# Base.net
KiCad netlist of a schematic drawn in EAGLE
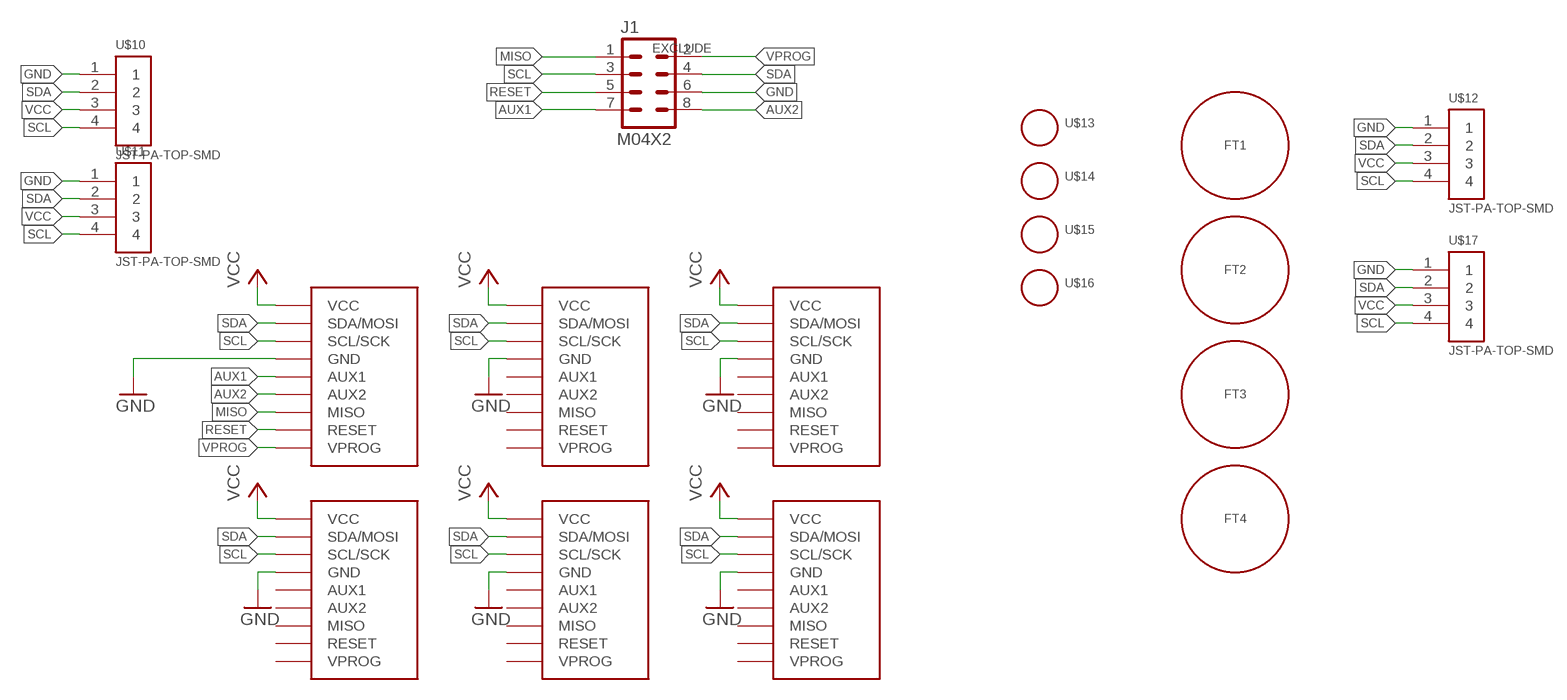
[diagram p0: schematic, sheet 1]

(export (version "E")
  (design (tool "Eeschema 10.0.6"))
  (components
    (comp (ref "FT1")
      (value "FOOT")
      (footprint "eagle-import:FOOT")
      (fields (field (name "PARTNUM") "SJ6553"))
      (libsource (lib "eagle-import") (part "FOOT"))
    )
    (comp (ref "FT2")
      (value "FOOT")
      (footprint "eagle-import:FOOT")
      (fields (field (name "PARTNUM") "SJ6553"))
      (libsource (lib "eagle-import") (part "FOOT"))
    )
    (comp (ref "FT3")
      (value "FOOT")
      (footprint "eagle-import:FOOT")
      (fields (field (name "PARTNUM") "SJ6553"))
      (libsource (lib "eagle-import") (part "FOOT"))
    )
    (comp (ref "FT4")
      (value "FOOT")
      (footprint "eagle-import:FOOT")
      (fields (field (name "PARTNUM") "SJ6553"))
      (libsource (lib "eagle-import") (part "FOOT"))
    )
    (comp (ref "J1")
      (value "M04X2")
      (footprint "eagle-import:2X4")
      (fields (field (name "PARTNUM") "EXCLUDE"))
      (libsource (lib "eagle-import") (part "M04X2"))
    )
    (comp (ref "U$1")
      (value "MAGBASE-V2")
      (footprint "eagle-import:MAGBASE-V2")
      (libsource (lib "eagle-import") (part "MAGBASE-V2"))
    )
    (comp (ref "U$2")
      (value "MAGBASE-V2")
      (footprint "eagle-import:MAGBASE-V2")
      (libsource (lib "eagle-import") (part "MAGBASE-V2"))
    )
    (comp (ref "U$3")
      (value "MAGBASE-V2")
      (footprint "eagle-import:MAGBASE-V2")
      (libsource (lib "eagle-import") (part "MAGBASE-V2"))
    )
    (comp (ref "U$4")
      (value "MAGBASE-V2")
      (footprint "eagle-import:MAGBASE-V2")
      (libsource (lib "eagle-import") (part "MAGBASE-V2"))
    )
    (comp (ref "U$5")
      (value "MAGBASE-V2")
      (footprint "eagle-import:MAGBASE-V2")
      (libsource (lib "eagle-import") (part "MAGBASE-V2"))
    )
    (comp (ref "U$6")
      (value "MAGBASE-V2")
      (footprint "eagle-import:MAGBASE-V2")
      (libsource (lib "eagle-import") (part "MAGBASE-V2"))
    )
    (comp (ref "U$10")
      (value "JST-PA-TOP-SMD")
      (footprint "eagle-import:JST-PA-TOP-SMD")
      (fields (field (name "PARTNUM") "BM04B-PASS-1-TFT(LF)(SN)"))
      (libsource (lib "eagle-import") (part "JST-PA-TOP-SMD"))
    )
    (comp (ref "U$11")
      (value "JST-PA-TOP-SMD")
      (footprint "eagle-import:JST-PA-TOP-SMD")
      (fields (field (name "PARTNUM") "BM04B-PASS-1-TFT(LF)(SN)"))
      (libsource (lib "eagle-import") (part "JST-PA-TOP-SMD"))
    )
    (comp (ref "U$12")
      (value "JST-PA-TOP-SMD")
      (footprint "eagle-import:JST-PA-TOP-SMD")
      (fields (field (name "PARTNUM") "BM04B-PASS-1-TFT(LF)(SN)"))
      (libsource (lib "eagle-import") (part "JST-PA-TOP-SMD"))
    )
    (comp (ref "U$13")
      (value "HOLE#4")
      (footprint "eagle-import:HOLE-#4")
      (fields (field (name "PARTNUM") "EXCLUDE"))
      (libsource (lib "eagle-import") (part "HOLE#4"))
    )
    (comp (ref "U$14")
      (value "HOLE#4")
      (footprint "eagle-import:HOLE-#4")
      (fields (field (name "PARTNUM") "EXCLUDE"))
      (libsource (lib "eagle-import") (part "HOLE#4"))
    )
    (comp (ref "U$15")
      (value "HOLE#4")
      (footprint "eagle-import:HOLE-#4")
      (fields (field (name "PARTNUM") "EXCLUDE"))
      (libsource (lib "eagle-import") (part "HOLE#4"))
    )
    (comp (ref "U$16")
      (value "HOLE#4")
      (footprint "eagle-import:HOLE-#4")
      (fields (field (name "PARTNUM") "EXCLUDE"))
      (libsource (lib "eagle-import") (part "HOLE#4"))
    )
    (comp (ref "U$17")
      (value "JST-PA-TOP-SMD")
      (footprint "eagle-import:JST-PA-TOP-SMD")
      (fields (field (name "PARTNUM") "BM04B-PASS-1-TFT(LF)(SN)"))
      (libsource (lib "eagle-import") (part "JST-PA-TOP-SMD"))
    )
  )
  (nets
    (net (code "1") (name "AUX1") (class "Default")
      (node (ref "J1") (pin "7") (pinfunction "7_7") (pintype "passive"))
      (node (ref "U$1") (pin "AUX1") (pinfunction "AUX1_AUX1") (pintype "bidirectional"))
    )
    (net (code "2") (name "AUX2") (class "Default")
      (node (ref "J1") (pin "8") (pinfunction "8_8") (pintype "passive"))
      (node (ref "U$1") (pin "AUX2") (pinfunction "AUX2_AUX2") (pintype "bidirectional"))
    )
    (net (code "3") (name "GND") (class "Default")
      (node (ref "J1") (pin "6") (pinfunction "6_6") (pintype "passive"))
      (node (ref "U$1") (pin "GND") (pinfunction "GND_GND") (pintype "bidirectional"))
      (node (ref "U$10") (pin "1") (pinfunction "1_1") (pintype "bidirectional"))
      (node (ref "U$11") (pin "1") (pinfunction "1_1") (pintype "bidirectional"))
      (node (ref "U$12") (pin "1") (pinfunction "1_1") (pintype "bidirectional"))
      (node (ref "U$17") (pin "1") (pinfunction "1_1") (pintype "bidirectional"))
      (node (ref "U$2") (pin "GND") (pinfunction "GND_GND") (pintype "bidirectional"))
      (node (ref "U$3") (pin "GND") (pinfunction "GND_GND") (pintype "bidirectional"))
      (node (ref "U$4") (pin "GND") (pinfunction "GND_GND") (pintype "bidirectional"))
      (node (ref "U$5") (pin "GND") (pinfunction "GND_GND") (pintype "bidirectional"))
      (node (ref "U$6") (pin "GND") (pinfunction "GND_GND") (pintype "bidirectional"))
    )
    (net (code "4") (name "MISO") (class "Default")
      (node (ref "J1") (pin "1") (pinfunction "1_1") (pintype "passive"))
      (node (ref "U$1") (pin "MISO") (pinfunction "MISO_MISO") (pintype "bidirectional"))
    )
    (net (code "5") (name "RESET") (class "Default")
      (node (ref "J1") (pin "5") (pinfunction "5_5") (pintype "passive"))
      (node (ref "U$1") (pin "RESET") (pinfunction "RESET_RESET") (pintype "bidirectional"))
    )
    (net (code "6") (name "SCL") (class "Default")
      (node (ref "J1") (pin "3") (pinfunction "3_3") (pintype "passive"))
      (node (ref "U$1") (pin "SCL") (pinfunction "SCL/SCK_SCL") (pintype "bidirectional"))
      (node (ref "U$10") (pin "4") (pinfunction "4_4") (pintype "bidirectional"))
      (node (ref "U$11") (pin "4") (pinfunction "4_4") (pintype "bidirectional"))
      (node (ref "U$12") (pin "4") (pinfunction "4_4") (pintype "bidirectional"))
      (node (ref "U$17") (pin "4") (pinfunction "4_4") (pintype "bidirectional"))
      (node (ref "U$2") (pin "SCL") (pinfunction "SCL/SCK_SCL") (pintype "bidirectional"))
      (node (ref "U$3") (pin "SCL") (pinfunction "SCL/SCK_SCL") (pintype "bidirectional"))
      (node (ref "U$4") (pin "SCL") (pinfunction "SCL/SCK_SCL") (pintype "bidirectional"))
      (node (ref "U$5") (pin "SCL") (pinfunction "SCL/SCK_SCL") (pintype "bidirectional"))
      (node (ref "U$6") (pin "SCL") (pinfunction "SCL/SCK_SCL") (pintype "bidirectional"))
    )
    (net (code "7") (name "SDA") (class "Default")
      (node (ref "J1") (pin "4") (pinfunction "4_4") (pintype "passive"))
      (node (ref "U$1") (pin "SDA") (pinfunction "SDA/MOSI_SDA") (pintype "bidirectional"))
      (node (ref "U$10") (pin "2") (pinfunction "2_2") (pintype "bidirectional"))
      (node (ref "U$11") (pin "2") (pinfunction "2_2") (pintype "bidirectional"))
      (node (ref "U$12") (pin "2") (pinfunction "2_2") (pintype "bidirectional"))
      (node (ref "U$17") (pin "2") (pinfunction "2_2") (pintype "bidirectional"))
      (node (ref "U$2") (pin "SDA") (pinfunction "SDA/MOSI_SDA") (pintype "bidirectional"))
      (node (ref "U$3") (pin "SDA") (pinfunction "SDA/MOSI_SDA") (pintype "bidirectional"))
      (node (ref "U$4") (pin "SDA") (pinfunction "SDA/MOSI_SDA") (pintype "bidirectional"))
      (node (ref "U$5") (pin "SDA") (pinfunction "SDA/MOSI_SDA") (pintype "bidirectional"))
      (node (ref "U$6") (pin "SDA") (pinfunction "SDA/MOSI_SDA") (pintype "bidirectional"))
    )
    (net (code "8") (name "VCC") (class "Default")
      (node (ref "U$1") (pin "VCC") (pinfunction "VCC_VCC") (pintype "bidirectional"))
      (node (ref "U$10") (pin "3") (pinfunction "3_3") (pintype "bidirectional"))
      (node (ref "U$11") (pin "3") (pinfunction "3_3") (pintype "bidirectional"))
      (node (ref "U$12") (pin "3") (pinfunction "3_3") (pintype "bidirectional"))
      (node (ref "U$17") (pin "3") (pinfunction "3_3") (pintype "bidirectional"))
      (node (ref "U$2") (pin "VCC") (pinfunction "VCC_VCC") (pintype "bidirectional"))
      (node (ref "U$3") (pin "VCC") (pinfunction "VCC_VCC") (pintype "bidirectional"))
      (node (ref "U$4") (pin "VCC") (pinfunction "VCC_VCC") (pintype "bidirectional"))
      (node (ref "U$5") (pin "VCC") (pinfunction "VCC_VCC") (pintype "bidirectional"))
      (node (ref "U$6") (pin "VCC") (pinfunction "VCC_VCC") (pintype "bidirectional"))
    )
    (net (code "9") (name "VPROG") (class "Default")
      (node (ref "J1") (pin "2") (pinfunction "2_2") (pintype "passive"))
      (node (ref "U$1") (pin "VPROG") (pinfunction "VPROG_VPROG") (pintype "bidirectional"))
    )
    (net (code "10") (name "unconnected-(U$2-PadAUX1)") (class "Default")
      (node (ref "U$2") (pin "AUX1") (pinfunction "AUX1_AUX1") (pintype "bidirectional"))
    )
    (net (code "11") (name "unconnected-(U$2-PadAUX2)") (class "Default")
      (node (ref "U$2") (pin "AUX2") (pinfunction "AUX2_AUX2") (pintype "bidirectional"))
    )
    (net (code "12") (name "unconnected-(U$2-PadMISO)") (class "Default")
      (node (ref "U$2") (pin "MISO") (pinfunction "MISO_MISO") (pintype "bidirectional"))
    )
    (net (code "13") (name "unconnected-(U$2-PadRESET)") (class "Default")
      (node (ref "U$2") (pin "RESET") (pinfunction "RESET_RESET") (pintype "bidirectional"))
    )
    (net (code "14") (name "unconnected-(U$2-PadVPROG)") (class "Default")
      (node (ref "U$2") (pin "VPROG") (pinfunction "VPROG_VPROG") (pintype "bidirectional"))
    )
    (net (code "15") (name "unconnected-(U$3-PadAUX1)") (class "Default")
      (node (ref "U$3") (pin "AUX1") (pinfunction "AUX1_AUX1") (pintype "bidirectional"))
    )
    (net (code "16") (name "unconnected-(U$3-PadAUX2)") (class "Default")
      (node (ref "U$3") (pin "AUX2") (pinfunction "AUX2_AUX2") (pintype "bidirectional"))
    )
    (net (code "17") (name "unconnected-(U$3-PadMISO)") (class "Default")
      (node (ref "U$3") (pin "MISO") (pinfunction "MISO_MISO") (pintype "bidirectional"))
    )
    (net (code "18") (name "unconnected-(U$3-PadRESET)") (class "Default")
      (node (ref "U$3") (pin "RESET") (pinfunction "RESET_RESET") (pintype "bidirectional"))
    )
    (net (code "19") (name "unconnected-(U$3-PadVPROG)") (class "Default")
      (node (ref "U$3") (pin "VPROG") (pinfunction "VPROG_VPROG") (pintype "bidirectional"))
    )
    (net (code "20") (name "unconnected-(U$4-PadAUX1)") (class "Default")
      (node (ref "U$4") (pin "AUX1") (pinfunction "AUX1_AUX1") (pintype "bidirectional"))
    )
    (net (code "21") (name "unconnected-(U$4-PadAUX2)") (class "Default")
      (node (ref "U$4") (pin "AUX2") (pinfunction "AUX2_AUX2") (pintype "bidirectional"))
    )
    (net (code "22") (name "unconnected-(U$4-PadMISO)") (class "Default")
      (node (ref "U$4") (pin "MISO") (pinfunction "MISO_MISO") (pintype "bidirectional"))
    )
    (net (code "23") (name "unconnected-(U$4-PadRESET)") (class "Default")
      (node (ref "U$4") (pin "RESET") (pinfunction "RESET_RESET") (pintype "bidirectional"))
    )
    (net (code "24") (name "unconnected-(U$4-PadVPROG)") (class "Default")
      (node (ref "U$4") (pin "VPROG") (pinfunction "VPROG_VPROG") (pintype "bidirectional"))
    )
    (net (code "25") (name "unconnected-(U$5-PadAUX1)") (class "Default")
      (node (ref "U$5") (pin "AUX1") (pinfunction "AUX1_AUX1") (pintype "bidirectional"))
    )
    (net (code "26") (name "unconnected-(U$5-PadAUX2)") (class "Default")
      (node (ref "U$5") (pin "AUX2") (pinfunction "AUX2_AUX2") (pintype "bidirectional"))
    )
    (net (code "27") (name "unconnected-(U$5-PadMISO)") (class "Default")
      (node (ref "U$5") (pin "MISO") (pinfunction "MISO_MISO") (pintype "bidirectional"))
    )
    (net (code "28") (name "unconnected-(U$5-PadRESET)") (class "Default")
      (node (ref "U$5") (pin "RESET") (pinfunction "RESET_RESET") (pintype "bidirectional"))
    )
    (net (code "29") (name "unconnected-(U$5-PadVPROG)") (class "Default")
      (node (ref "U$5") (pin "VPROG") (pinfunction "VPROG_VPROG") (pintype "bidirectional"))
    )
    (net (code "30") (name "unconnected-(U$6-PadAUX1)") (class "Default")
      (node (ref "U$6") (pin "AUX1") (pinfunction "AUX1_AUX1") (pintype "bidirectional"))
    )
    (net (code "31") (name "unconnected-(U$6-PadAUX2)") (class "Default")
      (node (ref "U$6") (pin "AUX2") (pinfunction "AUX2_AUX2") (pintype "bidirectional"))
    )
    (net (code "32") (name "unconnected-(U$6-PadMISO)") (class "Default")
      (node (ref "U$6") (pin "MISO") (pinfunction "MISO_MISO") (pintype "bidirectional"))
    )
    (net (code "33") (name "unconnected-(U$6-PadRESET)") (class "Default")
      (node (ref "U$6") (pin "RESET") (pinfunction "RESET_RESET") (pintype "bidirectional"))
    )
    (net (code "34") (name "unconnected-(U$6-PadVPROG)") (class "Default")
      (node (ref "U$6") (pin "VPROG") (pinfunction "VPROG_VPROG") (pintype "bidirectional"))
    )
    (net (code "35") (name "unconnected-(U$13-HOLE-PadP$1)") (class "Default")
      (node (ref "U$13") (pin "P$1") (pinfunction "HOLE_P$1") (pintype "bidirectional"))
    )
    (net (code "36") (name "unconnected-(U$14-HOLE-PadP$1)") (class "Default")
      (node (ref "U$14") (pin "P$1") (pinfunction "HOLE_P$1") (pintype "bidirectional"))
    )
    (net (code "37") (name "unconnected-(U$15-HOLE-PadP$1)") (class "Default")
      (node (ref "U$15") (pin "P$1") (pinfunction "HOLE_P$1") (pintype "bidirectional"))
    )
    (net (code "38") (name "unconnected-(U$16-HOLE-PadP$1)") (class "Default")
      (node (ref "U$16") (pin "P$1") (pinfunction "HOLE_P$1") (pintype "bidirectional"))
    )
  )
)
